# schematic.net
KiCad netlist of a schematic drawn in EasyEDA
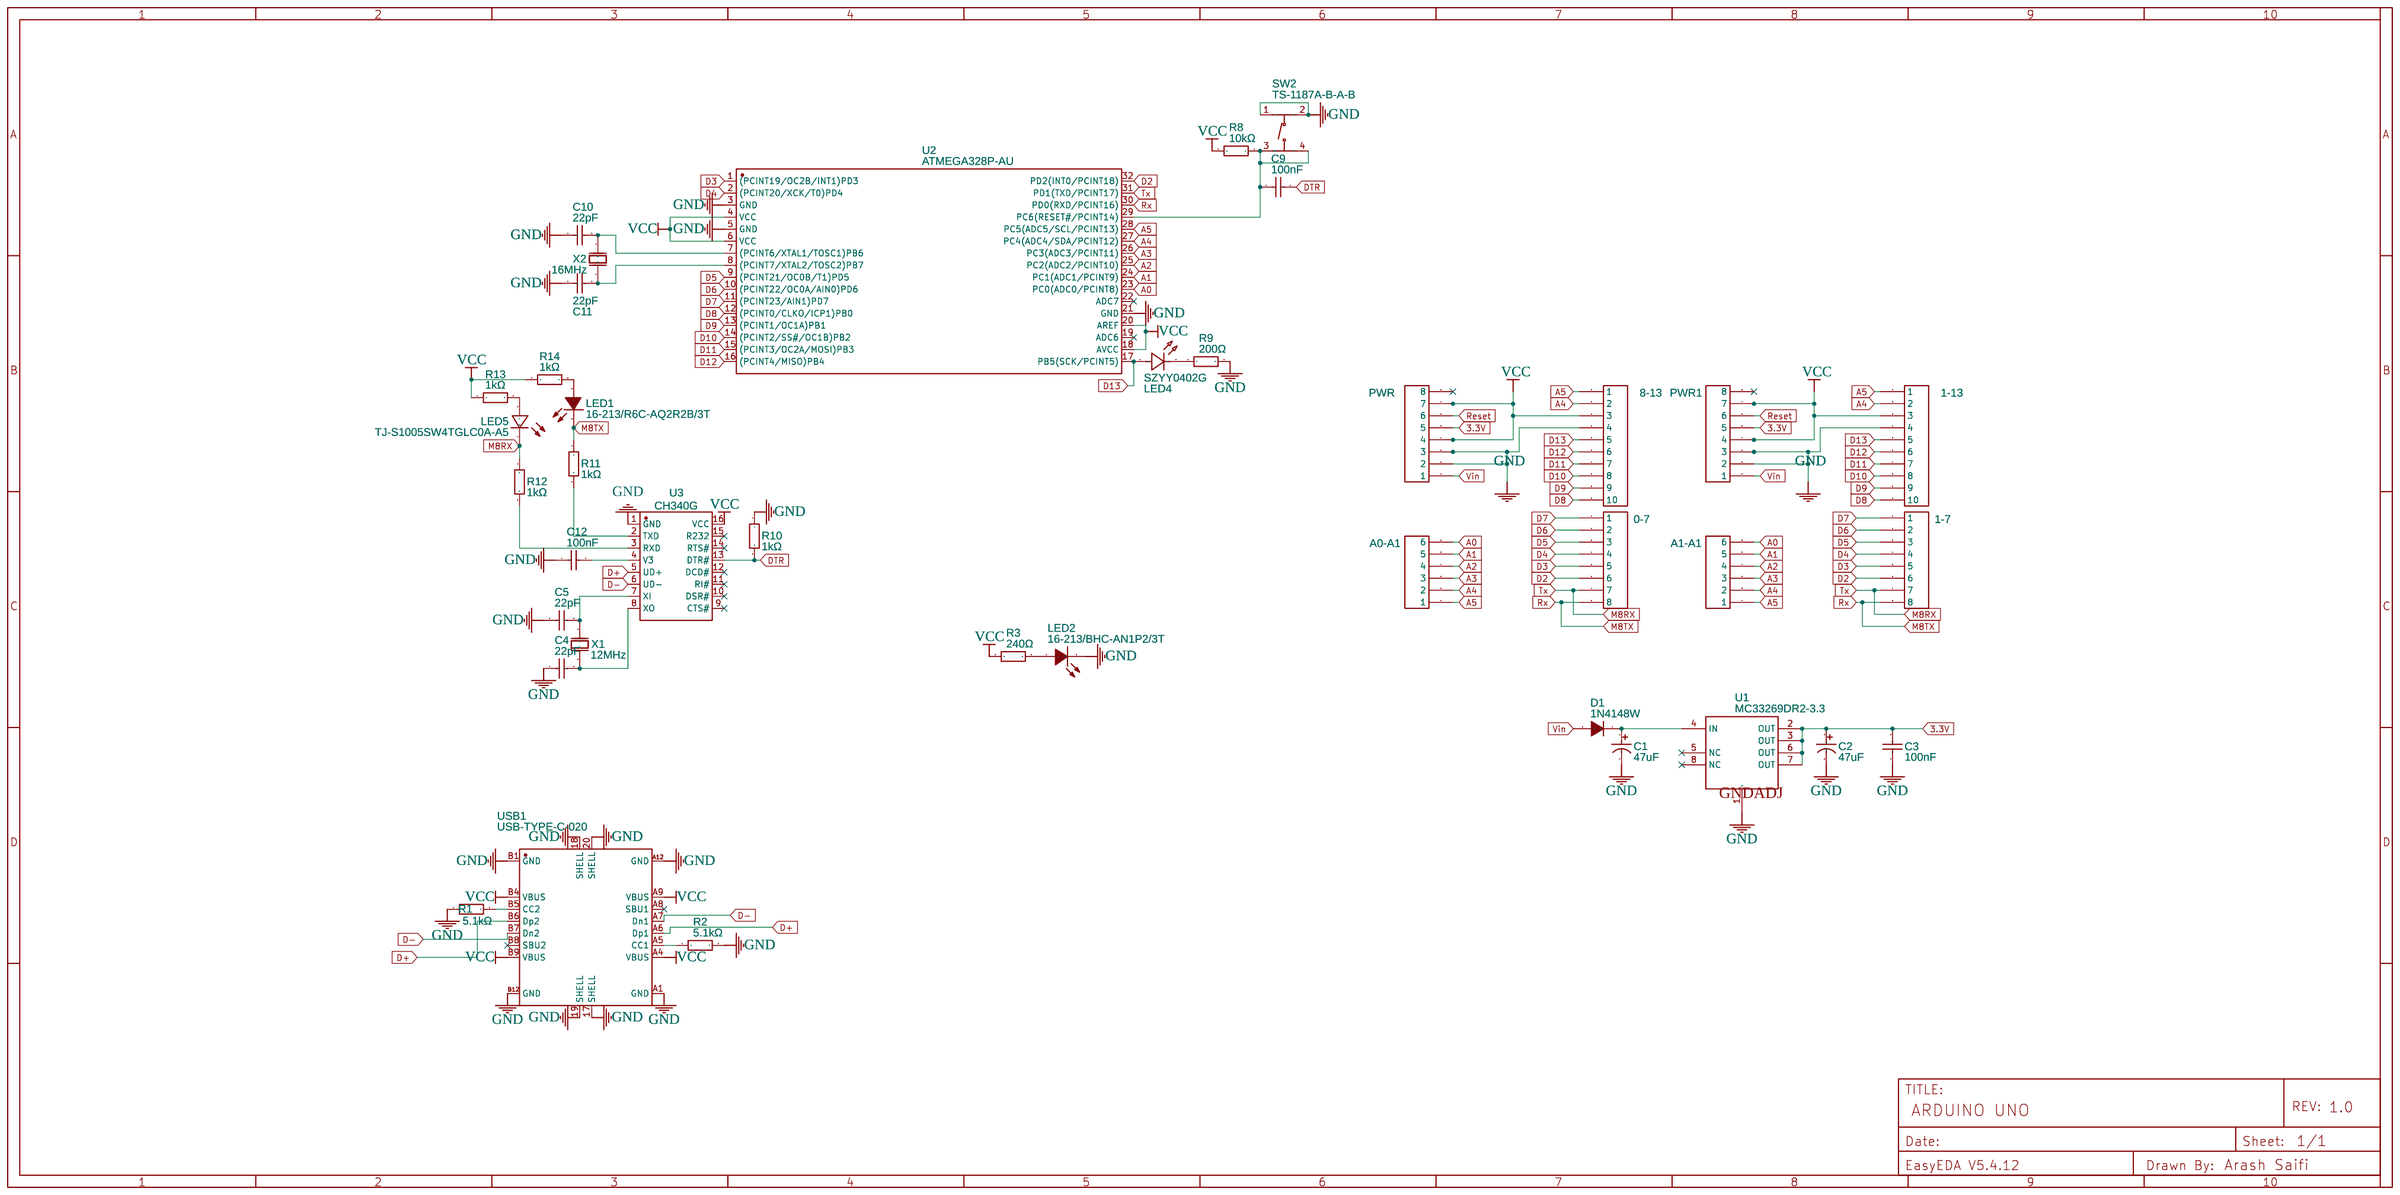
[diagram p0: schematic sheet]

(export (version "E")
  (design (tool "Eeschema 10.0.6"))
  (components
    (comp (ref "0-7")
      (value "0-7")
      (fields (field (name "Manufacturer Part") "Header2.54mm 1*8P") (field (name "Manufacturer") "ReliaPro"))
      (libsource (lib "") (part "Unknown_1315_280"))
    )
    (comp (ref "1-7")
      (value "0-7")
      (fields (field (name "Manufacturer Part") "Header2.54mm 1*8P") (field (name "Manufacturer") "ReliaPro"))
      (libsource (lib "") (part "Unknown_1565_280"))
    )
    (comp (ref "1-13")
      (value "8-Aref")
      (fields
        (field (name "Manufacturer Part") "Headers  Pins2.54mm1*10P")
        (field (name "Manufacturer") "ReliaPro")
      )
      (libsource (lib "") (part "Unknown_1565_185"))
    )
    (comp (ref "8-13")
      (value "8-Aref")
      (fields
        (field (name "Manufacturer Part") "Headers  Pins2.54mm1*10P")
        (field (name "Manufacturer") "ReliaPro")
      )
      (libsource (lib "") (part "Unknown_1315_185"))
    )
    (comp (ref "A0-A1")
      (value "Analogs")
      (fields
        (field (name "Manufacturer Part") "Header-Male-2.54_1x6")
        (field (name "Manufacturer") "BOOMELE")
      )
      (libsource (lib "") (part "Unknown_1190_300"))
    )
    (comp (ref "A1-A1")
      (value "Analogs")
      (fields
        (field (name "Manufacturer Part") "Header-Male-2.54_1x6")
        (field (name "Manufacturer") "BOOMELE")
      )
      (libsource (lib "") (part "Unknown_1440_300"))
    )
    (comp (ref "C1")
      (value "47uF")
      (fields (field (name "Manufacturer Part") "RVE1C470M0505") (field (name "Manufacturer") "ROQANG(容强)"))
      (libsource (lib "") (part "RVE1C470M0505"))
    )
    (comp (ref "C2")
      (value "47uF")
      (fields (field (name "Manufacturer Part") "RVE1C470M0505") (field (name "Manufacturer") "ROQANG(容强)"))
      (libsource (lib "") (part "RVE1C470M0505"))
    )
    (comp (ref "C3")
      (value "100nF")
      (fields
        (field (name "Manufacturer Part") "CL05B104KO5NNNC")
        (field (name "Manufacturer") "SAMSUNG(三星)")
      )
      (libsource (lib "") (part "CL05B104KO5NNNC_1"))
    )
    (comp (ref "C4")
      (value "22pF")
      (fields (field (name "Manufacturer Part") "0402CG220J500NT") (field (name "Manufacturer") "FH(风华)"))
      (libsource (lib "") (part "0402CG220J500NT_1"))
    )
    (comp (ref "C5")
      (value "22pF")
      (fields (field (name "Manufacturer Part") "0402CG220J500NT") (field (name "Manufacturer") "FH(风华)"))
      (libsource (lib "") (part "0402CG220J500NT_1"))
    )
    (comp (ref "C9")
      (value "100nF")
      (fields
        (field (name "Manufacturer Part") "CL05B104KO5NNNC")
        (field (name "Manufacturer") "SAMSUNG(三星)")
      )
      (libsource (lib "") (part "CL05B104KO5NNNC"))
    )
    (comp (ref "C10")
      (value "22pF")
      (fields (field (name "Manufacturer Part") "0402CG220J500NT") (field (name "Manufacturer") "FH(风华)"))
      (libsource (lib "") (part "0402CG220J500NT_1"))
    )
    (comp (ref "C11")
      (value "22pF")
      (fields (field (name "Manufacturer Part") "0402CG220J500NT") (field (name "Manufacturer") "FH(风华)"))
      (libsource (lib "") (part "0402CG220J500NT"))
    )
    (comp (ref "C12")
      (value "100nF")
      (fields
        (field (name "Manufacturer Part") "CL05B104KO5NNNC")
        (field (name "Manufacturer") "SAMSUNG(三星)")
      )
      (libsource (lib "") (part "CL05B104KO5NNNC"))
    )
    (comp (ref "D1")
      (value "1N4148W")
      (fields (field (name "Manufacturer") "HT(金誉)"))
      (libsource (lib "") (part "1N4148W"))
    )
    (comp (ref "LED1")
      (value "16-213/R6C-AQ2R2B/3T")
      (fields (field (name "Manufacturer") "EVERLIGHT(亿光)"))
      (libsource (lib "") (part "16-213/R6C-AQ2R2B/3T"))
    )
    (comp (ref "LED2")
      (value "16-213/BHC-AN1P2/3T")
      (fields (field (name "Manufacturer") "EVERLIGHT(亿光)"))
      (libsource (lib "") (part "16-213/BHC-AN1P2/3T"))
    )
    (comp (ref "LED4")
      (value "SZYY0402G")
      (fields (field (name "Manufacturer") "yongyu(永裕光电)"))
      (libsource (lib "") (part "SZYY0402G"))
    )
    (comp (ref "LED5")
      (value "TJ-S1005SW4TGLC0A-A5")
      (fields (field (name "Manufacturer") "TOGIALED(统佳)"))
      (libsource (lib "") (part "TJ-S1005SW4TGLC0A-A5"))
    )
    (comp (ref "PWR")
      (value "Powers")
      (fields (field (name "Manufacturer Part") "Header2.54mm 1*8P") (field (name "Manufacturer") "ReliaPro"))
      (libsource (lib "") (part "Unknown_1190_185"))
    )
    (comp (ref "PWR1")
      (value "Powers")
      (fields (field (name "Manufacturer Part") "Header2.54mm 1*8P") (field (name "Manufacturer") "ReliaPro"))
      (libsource (lib "") (part "Unknown_1440_185"))
    )
    (comp (ref "R1")
      (value "5.1kΩ")
      (fields
        (field (name "Manufacturer Part") "0402WGF5101TCE")
        (field (name "Manufacturer") "UNI-ROYAL(厚声)")
      )
      (libsource (lib "") (part "0402WGF5101TCE"))
    )
    (comp (ref "R2")
      (value "5.1kΩ")
      (fields
        (field (name "Manufacturer Part") "0402WGF5101TCE")
        (field (name "Manufacturer") "UNI-ROYAL(厚声)")
      )
      (libsource (lib "") (part "0402WGF5101TCE"))
    )
    (comp (ref "R3")
      (value "240Ω")
      (fields (field (name "Manufacturer Part") "RS-03K2400FT") (field (name "Manufacturer") "FH(风华)"))
      (libsource (lib "") (part "RS-03K2400FT"))
    )
    (comp (ref "R8")
      (value "10kΩ")
      (fields
        (field (name "Manufacturer Part") "0402WGF1002TCE")
        (field (name "Manufacturer") "UNI-ROYAL(厚声)")
      )
      (libsource (lib "") (part "0402WGF1002TCE"))
    )
    (comp (ref "R9")
      (value "200Ω")
      (fields
        (field (name "Manufacturer Part") "0402WGF2000TCE")
        (field (name "Manufacturer") "UNI-ROYAL(厚声)")
      )
      (libsource (lib "") (part "0402WGF2000TCE"))
    )
    (comp (ref "R10")
      (value "1kΩ")
      (fields
        (field (name "Manufacturer Part") "0402WGF1001TCE")
        (field (name "Manufacturer") "UNI-ROYAL(厚声)")
      )
      (libsource (lib "") (part "0402WGF1001TCE"))
    )
    (comp (ref "R11")
      (value "1kΩ")
      (fields
        (field (name "Manufacturer Part") "0402WGF1001TCE")
        (field (name "Manufacturer") "UNI-ROYAL(厚声)")
      )
      (libsource (lib "") (part "0402WGF1001TCE"))
    )
    (comp (ref "R12")
      (value "1kΩ")
      (fields
        (field (name "Manufacturer Part") "0402WGF1001TCE")
        (field (name "Manufacturer") "UNI-ROYAL(厚声)")
      )
      (libsource (lib "") (part "0402WGF1001TCE"))
    )
    (comp (ref "R13")
      (value "1kΩ")
      (fields
        (field (name "Manufacturer Part") "0402WGF1001TCE")
        (field (name "Manufacturer") "UNI-ROYAL(厚声)")
      )
      (libsource (lib "") (part "0402WGF1001TCE_1"))
    )
    (comp (ref "R14")
      (value "1kΩ")
      (fields
        (field (name "Manufacturer Part") "0402WGF1001TCE")
        (field (name "Manufacturer") "UNI-ROYAL(厚声)")
      )
      (libsource (lib "") (part "0402WGF1001TCE_1"))
    )
    (comp (ref "SW2")
      (value "TS-1187A-B-A-B")
      (fields (field (name "Manufacturer") "XKB Connectivity(中国星坤)"))
      (libsource (lib "") (part "TS-1187A-B-A-B"))
    )
    (comp (ref "U1")
      (value "MC33269DR2-3.3")
      (fields
        (field (name "Manufacturer Part") "MC33269DR2-3.3G")
        (field (name "Manufacturer") "onsemi(安森美)")
      )
      (libsource (lib "") (part "MC33269DR2-3.3"))
    )
    (comp (ref "U2")
      (value "ATMEGA328P-AU")
      (fields (field (name "Manufacturer") "MICROCHIP(美国微芯)"))
      (libsource (lib "") (part "ATMEGA328P-AU"))
    )
    (comp (ref "U3")
      (value "CH340G")
      (fields (field (name "Manufacturer") "WCH(南京沁恒)"))
      (libsource (lib "") (part "CH340G"))
    )
    (comp (ref "USB1")
      (value "USB-TYPE-C-020")
      (fields (field (name "Manufacturer") "DEALON(德艺隆)"))
      (libsource (lib "") (part "USB-TYPE-C-020"))
    )
    (comp (ref "X1")
      (value "12MHz")
      (fields (field (name "Manufacturer Part") "X49SM12MSB2SC") (field (name "Manufacturer") "YXC(扬兴晶振)"))
      (libsource (lib "") (part "X49SM12MSB2SC"))
    )
    (comp (ref "X2")
      (value "16MHz")
      (fields
        (field (name "Manufacturer Part") "49MD-16.000-20-20-20/A")
        (field (name "Manufacturer") "LIMING(利明)")
      )
      (libsource (lib "") (part "49MD-16.000-20-20-20/A"))
    )
  )
  (nets
    (net (code "1") (name "3.3V") (class "Default")
      (node (ref "C2") (pin "1") (pinfunction "1_1") (pintype "input"))
      (node (ref "C3") (pin "1") (pinfunction "1_1") (pintype "input"))
      (node (ref "PWR") (pin "5") (pinfunction "5_5") (pintype "input"))
      (node (ref "PWR1") (pin "5") (pinfunction "5_5") (pintype "input"))
      (node (ref "U1") (pin "2") (pinfunction "OUT_2") (pintype "passive"))
      (node (ref "U1") (pin "3") (pinfunction "OUT_3") (pintype "passive"))
      (node (ref "U1") (pin "6") (pinfunction "OUT_6") (pintype "passive"))
      (node (ref "U1") (pin "7") (pinfunction "OUT_7") (pintype "passive"))
    )
    (net (code "2") (name "A0") (class "Default")
      (node (ref "A0-A1") (pin "6") (pinfunction "6_6") (pintype "input"))
      (node (ref "A1-A1") (pin "6") (pinfunction "6_6") (pintype "input"))
      (node (ref "U2") (pin "23") (pinfunction "PC0(ADC0/PCINT8)_23") (pintype "unspecified"))
    )
    (net (code "3") (name "A1") (class "Default")
      (node (ref "A0-A1") (pin "5") (pinfunction "5_5") (pintype "input"))
      (node (ref "A1-A1") (pin "5") (pinfunction "5_5") (pintype "input"))
      (node (ref "U2") (pin "24") (pinfunction "PC1(ADC1/PCINT9)_24") (pintype "unspecified"))
    )
    (net (code "4") (name "A2") (class "Default")
      (node (ref "A0-A1") (pin "4") (pinfunction "4_4") (pintype "input"))
      (node (ref "A1-A1") (pin "4") (pinfunction "4_4") (pintype "input"))
      (node (ref "U2") (pin "25") (pinfunction "PC2(ADC2/PCINT10)_25") (pintype "unspecified"))
    )
    (net (code "5") (name "A3") (class "Default")
      (node (ref "A0-A1") (pin "3") (pinfunction "3_3") (pintype "input"))
      (node (ref "A1-A1") (pin "3") (pinfunction "3_3") (pintype "input"))
      (node (ref "U2") (pin "26") (pinfunction "PC3(ADC3/PCINT11)_26") (pintype "unspecified"))
    )
    (net (code "6") (name "A4") (class "Default")
      (node (ref "1-13") (pin "2") (pinfunction "2_2") (pintype "input"))
      (node (ref "8-13") (pin "2") (pinfunction "2_2") (pintype "input"))
      (node (ref "A0-A1") (pin "2") (pinfunction "2_2") (pintype "input"))
      (node (ref "A1-A1") (pin "2") (pinfunction "2_2") (pintype "input"))
      (node (ref "U2") (pin "27") (pinfunction "PC4(ADC4/SDA/PCINT12)_27") (pintype "unspecified"))
    )
    (net (code "7") (name "A5") (class "Default")
      (node (ref "1-13") (pin "1") (pinfunction "1_1") (pintype "input"))
      (node (ref "8-13") (pin "1") (pinfunction "1_1") (pintype "input"))
      (node (ref "A0-A1") (pin "1") (pinfunction "1_1") (pintype "input"))
      (node (ref "A1-A1") (pin "1") (pinfunction "1_1") (pintype "input"))
      (node (ref "U2") (pin "28") (pinfunction "PC5(ADC5/SCL/PCINT13)_28") (pintype "unspecified"))
    )
    (net (code "8") (name "D+") (class "Default")
      (node (ref "U3") (pin "5") (pinfunction "UD+_5") (pintype "unspecified"))
      (node (ref "USB1") (pin "A6") (pinfunction "Dp1_A6") (pintype "unspecified"))
      (node (ref "USB1") (pin "B6") (pinfunction "Dp2_B6") (pintype "unspecified"))
    )
    (net (code "9") (name "D-") (class "Default")
      (node (ref "U3") (pin "6") (pinfunction "UD-_6") (pintype "unspecified"))
      (node (ref "USB1") (pin "A7") (pinfunction "Dn1_A7") (pintype "unspecified"))
      (node (ref "USB1") (pin "B7") (pinfunction "Dn2_B7") (pintype "unspecified"))
    )
    (net (code "10") (name "D2") (class "Default")
      (node (ref "0-7") (pin "6") (pinfunction "6_6") (pintype "input"))
      (node (ref "1-7") (pin "6") (pinfunction "6_6") (pintype "input"))
      (node (ref "U2") (pin "32") (pinfunction "PD2(INT0/PCINT18)_32") (pintype "unspecified"))
    )
    (net (code "11") (name "D3") (class "Default")
      (node (ref "0-7") (pin "5") (pinfunction "5_5") (pintype "input"))
      (node (ref "1-7") (pin "5") (pinfunction "5_5") (pintype "input"))
      (node (ref "U2") (pin "1") (pinfunction "(PCINT19/OC2B/INT1)PD3_1") (pintype "unspecified"))
    )
    (net (code "12") (name "D4") (class "Default")
      (node (ref "0-7") (pin "4") (pinfunction "4_4") (pintype "input"))
      (node (ref "1-7") (pin "4") (pinfunction "4_4") (pintype "input"))
      (node (ref "U2") (pin "2") (pinfunction "(PCINT20/XCK/T0)PD4_2") (pintype "unspecified"))
    )
    (net (code "13") (name "D5") (class "Default")
      (node (ref "0-7") (pin "3") (pinfunction "3_3") (pintype "input"))
      (node (ref "1-7") (pin "3") (pinfunction "3_3") (pintype "input"))
      (node (ref "U2") (pin "9") (pinfunction "(PCINT21/OC0B/T1)PD5_9") (pintype "unspecified"))
    )
    (net (code "14") (name "D6") (class "Default")
      (node (ref "0-7") (pin "2") (pinfunction "2_2") (pintype "input"))
      (node (ref "1-7") (pin "2") (pinfunction "2_2") (pintype "input"))
      (node (ref "U2") (pin "10") (pinfunction "(PCINT22/OC0A/AIN0)PD6_10") (pintype "unspecified"))
    )
    (net (code "15") (name "D7") (class "Default")
      (node (ref "0-7") (pin "1") (pinfunction "1_1") (pintype "input"))
      (node (ref "1-7") (pin "1") (pinfunction "1_1") (pintype "input"))
      (node (ref "U2") (pin "11") (pinfunction "(PCINT23/AIN1)PD7_11") (pintype "unspecified"))
    )
    (net (code "16") (name "D8") (class "Default")
      (node (ref "1-13") (pin "10") (pinfunction "10_10") (pintype "input"))
      (node (ref "8-13") (pin "10") (pinfunction "10_10") (pintype "input"))
      (node (ref "U2") (pin "12") (pinfunction "(PCINT0/CLKO/ICP1)PB0_12") (pintype "unspecified"))
    )
    (net (code "17") (name "D9") (class "Default")
      (node (ref "1-13") (pin "9") (pinfunction "9_9") (pintype "input"))
      (node (ref "8-13") (pin "9") (pinfunction "9_9") (pintype "input"))
      (node (ref "U2") (pin "13") (pinfunction "(PCINT1/OC1A)PB1_13") (pintype "unspecified"))
    )
    (net (code "18") (name "D10") (class "Default")
      (node (ref "1-13") (pin "8") (pinfunction "8_8") (pintype "input"))
      (node (ref "8-13") (pin "8") (pinfunction "8_8") (pintype "input"))
      (node (ref "U2") (pin "14") (pinfunction "(PCINT2/SS#/OC1B)PB2_14") (pintype "unspecified"))
    )
    (net (code "19") (name "D11") (class "Default")
      (node (ref "1-13") (pin "7") (pinfunction "7_7") (pintype "input"))
      (node (ref "8-13") (pin "7") (pinfunction "7_7") (pintype "input"))
      (node (ref "U2") (pin "15") (pinfunction "(PCINT3/OC2A/MOSI)PB3_15") (pintype "unspecified"))
    )
    (net (code "20") (name "D12") (class "Default")
      (node (ref "1-13") (pin "6") (pinfunction "6_6") (pintype "input"))
      (node (ref "8-13") (pin "6") (pinfunction "6_6") (pintype "input"))
      (node (ref "U2") (pin "16") (pinfunction "(PCINT4/MISO)PB4_16") (pintype "unspecified"))
    )
    (net (code "21") (name "D13") (class "Default")
      (node (ref "1-13") (pin "5") (pinfunction "5_5") (pintype "input"))
      (node (ref "8-13") (pin "5") (pinfunction "5_5") (pintype "input"))
      (node (ref "LED4") (pin "1") (pinfunction "A_1") (pintype "unspecified"))
      (node (ref "U2") (pin "17") (pinfunction "PB5(SCK/PCINT5)_17") (pintype "unspecified"))
    )
    (net (code "22") (name "DTR") (class "Default")
      (node (ref "C9") (pin "2") (pinfunction "2_2") (pintype "input"))
      (node (ref "R10") (pin "2") (pinfunction "2_2") (pintype "input"))
      (node (ref "U3") (pin "13") (pinfunction "DTR#_13") (pintype "unspecified"))
    )
    (net (code "23") (name "GND") (class "Default")
      (node (ref "1-13") (pin "4") (pinfunction "4_4") (pintype "input"))
      (node (ref "8-13") (pin "4") (pinfunction "4_4") (pintype "input"))
      (node (ref "C1") (pin "2") (pinfunction "2_2") (pintype "input"))
      (node (ref "C10") (pin "1") (pinfunction "1_1") (pintype "input"))
      (node (ref "C11") (pin "1") (pinfunction "1_1") (pintype "input"))
      (node (ref "C12") (pin "1") (pinfunction "1_1") (pintype "input"))
      (node (ref "C2") (pin "2") (pinfunction "2_2") (pintype "input"))
      (node (ref "C3") (pin "2") (pinfunction "2_2") (pintype "input"))
      (node (ref "C4") (pin "1") (pinfunction "1_1") (pintype "input"))
      (node (ref "C5") (pin "1") (pinfunction "1_1") (pintype "input"))
      (node (ref "LED2") (pin "2") (pinfunction "K_2") (pintype "unspecified"))
      (node (ref "PWR") (pin "2") (pinfunction "2_2") (pintype "input"))
      (node (ref "PWR") (pin "3") (pinfunction "3_3") (pintype "input"))
      (node (ref "PWR1") (pin "2") (pinfunction "2_2") (pintype "input"))
      (node (ref "PWR1") (pin "3") (pinfunction "3_3") (pintype "input"))
      (node (ref "R1") (pin "1") (pinfunction "1_1") (pintype "input"))
      (node (ref "R10") (pin "1") (pinfunction "1_1") (pintype "input"))
      (node (ref "R2") (pin "2") (pinfunction "2_2") (pintype "input"))
      (node (ref "R9") (pin "2") (pinfunction "2_2") (pintype "input"))
      (node (ref "SW2") (pin "1") (pinfunction "A_1") (pintype "unspecified"))
      (node (ref "SW2") (pin "2") (pinfunction "B_2") (pintype "unspecified"))
      (node (ref "U1") (pin "1") (pinfunction "GNDADJ_1") (pintype "passive"))
      (node (ref "U2") (pin "21") (pinfunction "GND_21") (pintype "unspecified"))
      (node (ref "U2") (pin "3") (pinfunction "GND_3") (pintype "unspecified"))
      (node (ref "U2") (pin "5") (pinfunction "GND_5") (pintype "unspecified"))
      (node (ref "U3") (pin "1") (pinfunction "GND_1") (pintype "unspecified"))
      (node (ref "USB1") (pin "17") (pinfunction "SHELL_17") (pintype "unspecified"))
      (node (ref "USB1") (pin "18") (pinfunction "SHELL_18") (pintype "unspecified"))
      (node (ref "USB1") (pin "19") (pinfunction "SHELL_19") (pintype "unspecified"))
      (node (ref "USB1") (pin "20") (pinfunction "SHELL_20") (pintype "unspecified"))
      (node (ref "USB1") (pin "A1") (pinfunction "GND_A1") (pintype "unspecified"))
      (node (ref "USB1") (pin "A12") (pinfunction "GND_A12") (pintype "unspecified"))
      (node (ref "USB1") (pin "B1") (pinfunction "GND_B1") (pintype "unspecified"))
      (node (ref "USB1") (pin "B12") (pinfunction "GND_B12") (pintype "unspecified"))
    )
    (net (code "24") (name "M8RX") (class "Default")
      (node (ref "0-7") (pin "7") (pinfunction "7_7") (pintype "input"))
      (node (ref "1-7") (pin "7") (pinfunction "7_7") (pintype "input"))
      (node (ref "LED5") (pin "1") (pinfunction "C_1") (pintype "unspecified"))
      (node (ref "R12") (pin "1") (pinfunction "1_1") (pintype "input"))
      (node (ref "U2") (pin "31") (pinfunction "PD1(TXD/PCINT17)_31") (pintype "unspecified"))
    )
    (net (code "25") (name "M8TX") (class "Default")
      (node (ref "0-7") (pin "8") (pinfunction "8_8") (pintype "input"))
      (node (ref "1-7") (pin "8") (pinfunction "8_8") (pintype "input"))
      (node (ref "LED1") (pin "2") (pinfunction "K_2") (pintype "unspecified"))
      (node (ref "R11") (pin "1") (pinfunction "1_1") (pintype "input"))
      (node (ref "U2") (pin "30") (pinfunction "PD0(RXD/PCINT16)_30") (pintype "unspecified"))
    )
    (net (code "26") (name "Net-(D1-K)") (class "Default")
      (node (ref "C1") (pin "1") (pinfunction "1_1") (pintype "input"))
      (node (ref "D1") (pin "1") (pinfunction "K_1") (pintype "unspecified"))
      (node (ref "U1") (pin "4") (pinfunction "IN_4") (pintype "passive"))
    )
    (net (code "27") (name "Net-(LED1-A)") (class "Default")
      (node (ref "LED1") (pin "1") (pinfunction "A_1") (pintype "unspecified"))
      (node (ref "R14") (pin "2") (pinfunction "2_2") (pintype "input"))
    )
    (net (code "28") (name "Net-(LED2-A)") (class "Default")
      (node (ref "LED2") (pin "1") (pinfunction "A_1") (pintype "unspecified"))
      (node (ref "R3") (pin "2") (pinfunction "2_2") (pintype "unspecified"))
    )
    (net (code "29") (name "Net-(LED4-K)") (class "Default")
      (node (ref "LED4") (pin "2") (pinfunction "K_2") (pintype "unspecified"))
      (node (ref "R9") (pin "1") (pinfunction "1_1") (pintype "input"))
    )
    (net (code "30") (name "Net-(LED5-A)") (class "Default")
      (node (ref "LED5") (pin "2") (pinfunction "A_2") (pintype "unspecified"))
      (node (ref "R13") (pin "2") (pinfunction "2_2") (pintype "input"))
    )
    (net (code "31") (name "Net-(SW2-C)") (class "Default")
      (node (ref "C9") (pin "1") (pinfunction "1_1") (pintype "input"))
      (node (ref "R8") (pin "2") (pinfunction "2_2") (pintype "input"))
      (node (ref "SW2") (pin "3") (pinfunction "C_3") (pintype "unspecified"))
      (node (ref "SW2") (pin "4") (pinfunction "D_4") (pintype "unspecified"))
      (node (ref "U2") (pin "29") (pinfunction "PC6(RESET#/PCINT14)_29") (pintype "unspecified"))
    )
    (net (code "32") (name "Net-(U2-(PCINT6{slash}XTAL1{slash}TOSC1)PB6)") (class "Default")
      (node (ref "C10") (pin "2") (pinfunction "2_2") (pintype "input"))
      (node (ref "U2") (pin "7") (pinfunction "(PCINT6/XTAL1/TOSC1)PB6_7") (pintype "unspecified"))
      (node (ref "X2") (pin "2") (pinfunction "OSC2_2") (pintype "input"))
    )
    (net (code "33") (name "Net-(U2-(PCINT7{slash}XTAL2{slash}TOSC2)PB7)") (class "Default")
      (node (ref "C11") (pin "2") (pinfunction "2_2") (pintype "input"))
      (node (ref "U2") (pin "8") (pinfunction "(PCINT7/XTAL2/TOSC2)PB7_8") (pintype "unspecified"))
      (node (ref "X2") (pin "1") (pinfunction "OSC1_1") (pintype "input"))
    )
    (net (code "34") (name "Net-(U3-RXD)") (class "Default")
      (node (ref "R12") (pin "2") (pinfunction "2_2") (pintype "input"))
      (node (ref "U3") (pin "3") (pinfunction "RXD_3") (pintype "unspecified"))
    )
    (net (code "35") (name "Net-(U3-TXD)") (class "Default")
      (node (ref "R11") (pin "2") (pinfunction "2_2") (pintype "input"))
      (node (ref "U3") (pin "2") (pinfunction "TXD_2") (pintype "unspecified"))
    )
    (net (code "36") (name "Net-(U3-V3)") (class "Default")
      (node (ref "C12") (pin "2") (pinfunction "2_2") (pintype "input"))
      (node (ref "U3") (pin "4") (pinfunction "V3_4") (pintype "unspecified"))
    )
    (net (code "37") (name "Net-(U3-XI)") (class "Default")
      (node (ref "C5") (pin "2") (pinfunction "2_2") (pintype "input"))
      (node (ref "U3") (pin "7") (pinfunction "XI_7") (pintype "unspecified"))
      (node (ref "X1") (pin "1") (pinfunction "OSC1_1") (pintype "input"))
    )
    (net (code "38") (name "Net-(U3-XO)") (class "Default")
      (node (ref "C4") (pin "2") (pinfunction "2_2") (pintype "input"))
      (node (ref "U3") (pin "8") (pinfunction "XO_8") (pintype "unspecified"))
      (node (ref "X1") (pin "2") (pinfunction "OSC2_2") (pintype "input"))
    )
    (net (code "39") (name "Net-(USB1-CC1)") (class "Default")
      (node (ref "R2") (pin "1") (pinfunction "1_1") (pintype "input"))
      (node (ref "USB1") (pin "A5") (pinfunction "CC1_A5") (pintype "unspecified"))
    )
    (net (code "40") (name "Net-(USB1-CC2)") (class "Default")
      (node (ref "R1") (pin "2") (pinfunction "2_2") (pintype "input"))
      (node (ref "USB1") (pin "B5") (pinfunction "CC2_B5") (pintype "unspecified"))
    )
    (net (code "41") (name "Reset") (class "Default")
      (node (ref "PWR") (pin "6") (pinfunction "6_6") (pintype "input"))
      (node (ref "PWR1") (pin "6") (pinfunction "6_6") (pintype "input"))
    )
    (net (code "42") (name "VCC") (class "Default")
      (node (ref "1-13") (pin "3") (pinfunction "3_3") (pintype "input"))
      (node (ref "8-13") (pin "3") (pinfunction "3_3") (pintype "input"))
      (node (ref "PWR") (pin "4") (pinfunction "4_4") (pintype "input"))
      (node (ref "PWR") (pin "7") (pinfunction "7_7") (pintype "input"))
      (node (ref "PWR1") (pin "4") (pinfunction "4_4") (pintype "input"))
      (node (ref "PWR1") (pin "7") (pinfunction "7_7") (pintype "input"))
      (node (ref "R13") (pin "1") (pinfunction "1_1") (pintype "input"))
      (node (ref "R14") (pin "1") (pinfunction "1_1") (pintype "input"))
      (node (ref "R3") (pin "1") (pinfunction "1_1") (pintype "unspecified"))
      (node (ref "R8") (pin "1") (pinfunction "1_1") (pintype "input"))
      (node (ref "U2") (pin "18") (pinfunction "AVCC_18") (pintype "unspecified"))
      (node (ref "U2") (pin "20") (pinfunction "AREF_20") (pintype "unspecified"))
      (node (ref "U2") (pin "4") (pinfunction "VCC_4") (pintype "unspecified"))
      (node (ref "U2") (pin "6") (pinfunction "VCC_6") (pintype "unspecified"))
      (node (ref "U3") (pin "16") (pinfunction "VCC_16") (pintype "unspecified"))
      (node (ref "USB1") (pin "A4") (pinfunction "VBUS_A4") (pintype "unspecified"))
      (node (ref "USB1") (pin "A9") (pinfunction "VBUS_A9") (pintype "unspecified"))
      (node (ref "USB1") (pin "B4") (pinfunction "VBUS_B4") (pintype "unspecified"))
      (node (ref "USB1") (pin "B9") (pinfunction "VBUS_B9") (pintype "unspecified"))
    )
    (net (code "43") (name "Vin") (class "Default")
      (node (ref "D1") (pin "2") (pinfunction "A_2") (pintype "unspecified"))
      (node (ref "PWR") (pin "1") (pinfunction "1_1") (pintype "input"))
      (node (ref "PWR1") (pin "1") (pinfunction "1_1") (pintype "input"))
    )
    (net (code "44") (name "unconnected-(PWR-Pad8)") (class "Default")
      (node (ref "PWR") (pin "8") (pinfunction "8_8") (pintype "input+no_connect"))
    )
    (net (code "45") (name "unconnected-(PWR1-Pad8)") (class "Default")
      (node (ref "PWR1") (pin "8") (pinfunction "8_8") (pintype "input+no_connect"))
    )
    (net (code "46") (name "unconnected-(U1-NC-Pad5)") (class "Default")
      (node (ref "U1") (pin "5") (pinfunction "NC_5") (pintype "unspecified+no_connect"))
    )
    (net (code "47") (name "unconnected-(U1-NC-Pad8)") (class "Default")
      (node (ref "U1") (pin "8") (pinfunction "NC_8") (pintype "unspecified+no_connect"))
    )
    (net (code "48") (name "unconnected-(U2-ADC6-Pad19)") (class "Default")
      (node (ref "U2") (pin "19") (pinfunction "ADC6_19") (pintype "unspecified+no_connect"))
    )
    (net (code "49") (name "unconnected-(U2-ADC7-Pad22)") (class "Default")
      (node (ref "U2") (pin "22") (pinfunction "ADC7_22") (pintype "unspecified+no_connect"))
    )
    (net (code "50") (name "unconnected-(U3-CTS#-Pad9)") (class "Default")
      (node (ref "U3") (pin "9") (pinfunction "CTS#_9") (pintype "unspecified+no_connect"))
    )
    (net (code "51") (name "unconnected-(U3-DCD#-Pad12)") (class "Default")
      (node (ref "U3") (pin "12") (pinfunction "DCD#_12") (pintype "unspecified+no_connect"))
    )
    (net (code "52") (name "unconnected-(U3-DSR#-Pad10)") (class "Default")
      (node (ref "U3") (pin "10") (pinfunction "DSR#_10") (pintype "unspecified+no_connect"))
    )
    (net (code "53") (name "unconnected-(U3-R232-Pad15)") (class "Default")
      (node (ref "U3") (pin "15") (pinfunction "R232_15") (pintype "unspecified+no_connect"))
    )
    (net (code "54") (name "unconnected-(U3-RI#-Pad11)") (class "Default")
      (node (ref "U3") (pin "11") (pinfunction "RI#_11") (pintype "unspecified+no_connect"))
    )
    (net (code "55") (name "unconnected-(U3-RTS#-Pad14)") (class "Default")
      (node (ref "U3") (pin "14") (pinfunction "RTS#_14") (pintype "unspecified+no_connect"))
    )
    (net (code "56") (name "unconnected-(USB1-SBU1-PadA8)") (class "Default")
      (node (ref "USB1") (pin "A8") (pinfunction "SBU1_A8") (pintype "unspecified+no_connect"))
    )
    (net (code "57") (name "unconnected-(USB1-SBU2-PadB8)") (class "Default")
      (node (ref "USB1") (pin "B8") (pinfunction "SBU2_B8") (pintype "unspecified+no_connect"))
    )
  )
)
